# EasyEda_Gateway.net
KiCad netlist of a schematic drawn in EasyEDA Pro
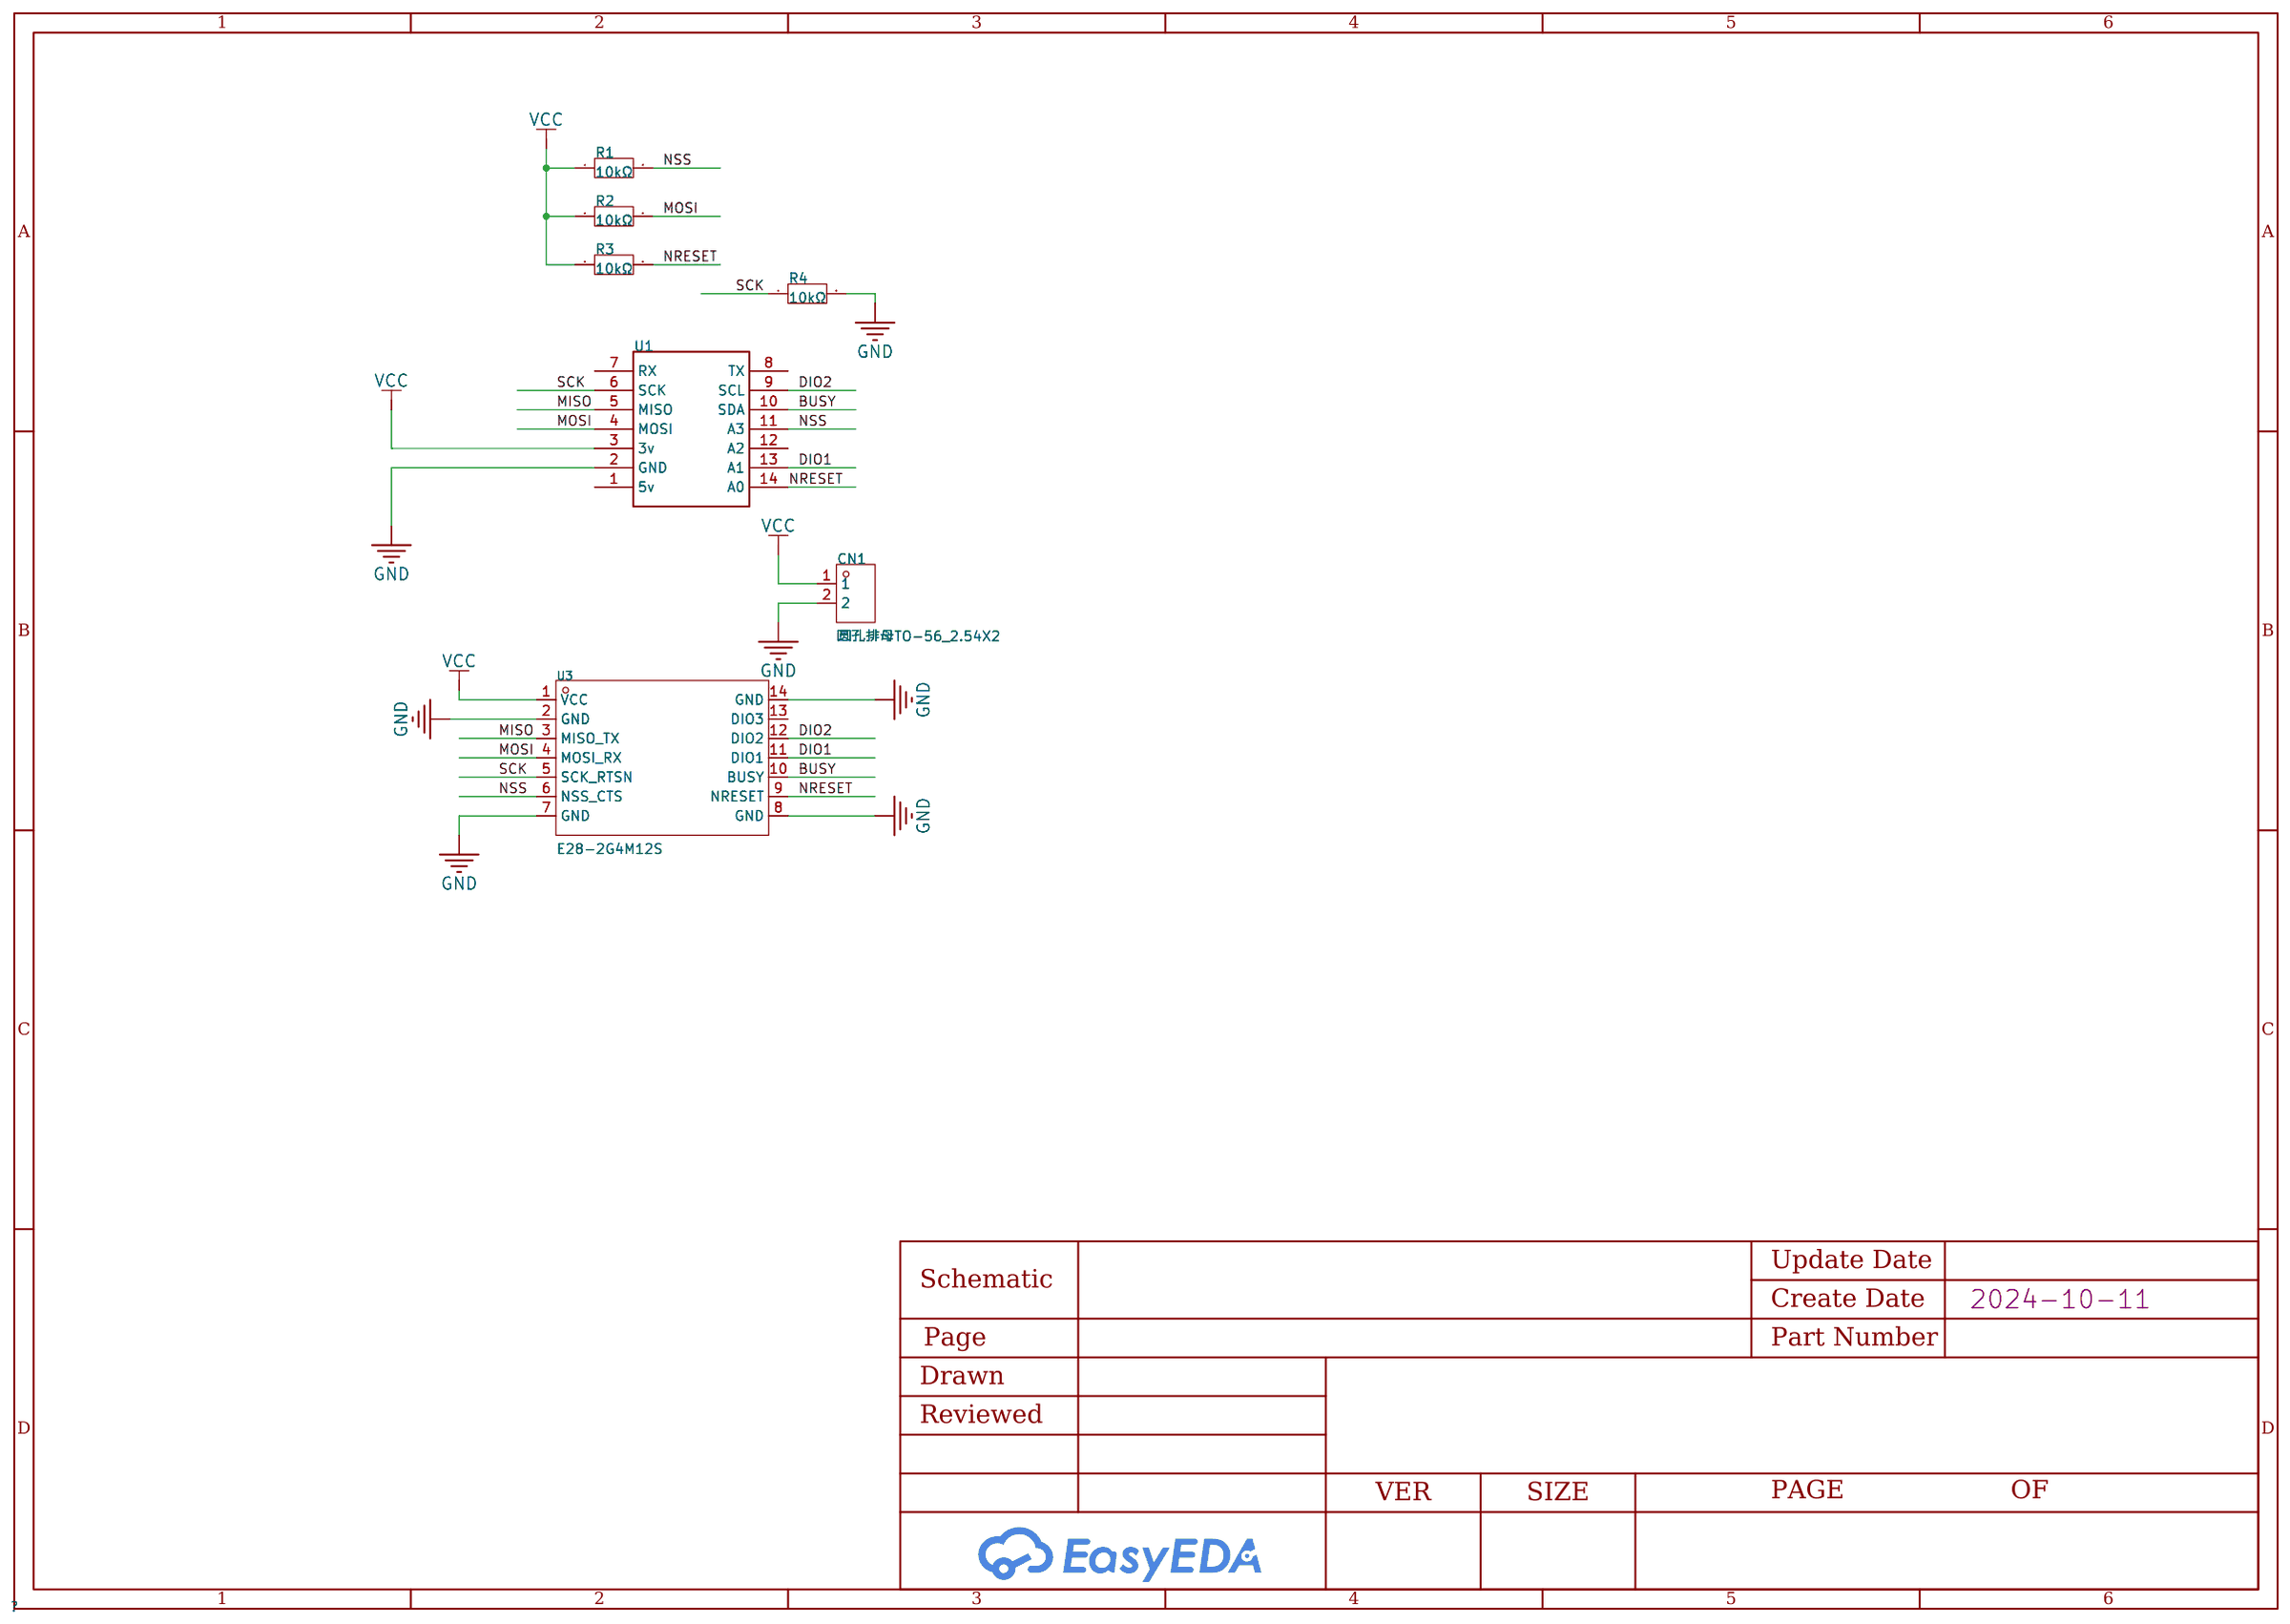
[diagram p0: schematic sheet]

(export (version "E")
  (design (tool "Eeschema 10.0.6"))
  (components
    (comp (ref "CN1")
      (value "圆孔排母TO-56_2.54X2")
      (footprint "easyedapro:CONN-TH_TO-56_2.54-2")
      (libsource (lib "easyedapro") (part "圆孔排母TO-56_2.54X2"))
    )
    (comp (ref "R1")
      (value "10kΩ")
      (footprint "easyedapro:R0603")
      (fields
        (field (name "Manufacturer Part") "RMCF0603FT1K00")
        (field (name "Manufacturer") "SEI(Stackpole Electronics Inc.)")
      )
      (libsource (lib "easyedapro") (part "RMCF0603FT1K00"))
    )
    (comp (ref "R2")
      (value "10kΩ")
      (footprint "easyedapro:R0603")
      (fields
        (field (name "Manufacturer Part") "RMCF0603FT1K00")
        (field (name "Manufacturer") "SEI(Stackpole Electronics Inc.)")
      )
      (libsource (lib "easyedapro") (part "RMCF0603FT1K00"))
    )
    (comp (ref "R3")
      (value "10kΩ")
      (footprint "easyedapro:R0603")
      (fields
        (field (name "Manufacturer Part") "RMCF0603FT1K00")
        (field (name "Manufacturer") "SEI(Stackpole Electronics Inc.)")
      )
      (libsource (lib "easyedapro") (part "RMCF0603FT1K00"))
    )
    (comp (ref "R4")
      (value "10kΩ")
      (footprint "easyedapro:R0603")
      (fields
        (field (name "Manufacturer Part") "RMCF0603FT1K00")
        (field (name "Manufacturer") "SEI(Stackpole Electronics Inc.)")
      )
      (libsource (lib "easyedapro") (part "RMCF0603FT1K00"))
    )
    (comp (ref "U1")
      (value "=ESP32-qtpy")
      (footprint "easyedapro:esp32-s2_qtpy")
      (libsource (lib "easyedapro") (part "esp32-s2_qtpy"))
    )
    (comp (ref "U3")
      (value "E28-2G4M12S")
      (footprint "easyedapro:WIRELM-SMD_E28-2G4M12S")
      (fields (field (name "Manufacturer") "EBYTE(亿佰特)"))
      (libsource (lib "easyedapro") (part "E28-2G4M12S"))
    )
  )
  (nets
    (net (code "1") (name "/BUSY") (class "Default")
      (node (ref "U1") (pin "10") (pinfunction "SDA_10") (pintype "input"))
      (node (ref "U3") (pin "10") (pinfunction "BUSY_10") (pintype "input"))
    )
    (net (code "2") (name "/DIO1") (class "Default")
      (node (ref "U1") (pin "13") (pinfunction "A1_13") (pintype "input"))
      (node (ref "U3") (pin "11") (pinfunction "DIO1_11") (pintype "input"))
    )
    (net (code "3") (name "/DIO2") (class "Default")
      (node (ref "U1") (pin "9") (pinfunction "SCL_9") (pintype "input"))
      (node (ref "U3") (pin "12") (pinfunction "DIO2_12") (pintype "input"))
    )
    (net (code "4") (name "/MISO") (class "Default")
      (node (ref "U1") (pin "5") (pinfunction "MISO_5") (pintype "input"))
      (node (ref "U3") (pin "3") (pinfunction "MISO_TX_3") (pintype "input"))
    )
    (net (code "5") (name "/MOSI") (class "Default")
      (node (ref "R2") (pin "2") (pinfunction "2_2") (pintype "input"))
      (node (ref "U1") (pin "4") (pinfunction "MOSI_4") (pintype "input"))
      (node (ref "U3") (pin "4") (pinfunction "MOSI_RX_4") (pintype "input"))
    )
    (net (code "6") (name "/NRESET") (class "Default")
      (node (ref "R3") (pin "2") (pinfunction "2_2") (pintype "input"))
      (node (ref "U1") (pin "14") (pinfunction "A0_14") (pintype "input"))
      (node (ref "U3") (pin "9") (pinfunction "NRESET_9") (pintype "input"))
    )
    (net (code "7") (name "/NSS") (class "Default")
      (node (ref "R1") (pin "2") (pinfunction "2_2") (pintype "input"))
      (node (ref "U1") (pin "11") (pinfunction "A3_11") (pintype "input"))
      (node (ref "U3") (pin "6") (pinfunction "NSS_CTS_6") (pintype "input"))
    )
    (net (code "8") (name "/SCK") (class "Default")
      (node (ref "R4") (pin "1") (pinfunction "1_1") (pintype "input"))
      (node (ref "U1") (pin "6") (pinfunction "SCK_6") (pintype "input"))
      (node (ref "U3") (pin "5") (pinfunction "SCK_RTSN_5") (pintype "input"))
    )
    (net (code "9") (name "GND") (class "Default")
      (node (ref "CN1") (pin "2") (pinfunction "2_2") (pintype "unspecified"))
      (node (ref "R4") (pin "2") (pinfunction "2_2") (pintype "input"))
      (node (ref "U1") (pin "2") (pinfunction "GND_2") (pintype "input"))
      (node (ref "U3") (pin "14") (pinfunction "GND_14") (pintype "input"))
      (node (ref "U3") (pin "2") (pinfunction "GND_2") (pintype "input"))
      (node (ref "U3") (pin "7") (pinfunction "GND_7") (pintype "input"))
      (node (ref "U3") (pin "8") (pinfunction "GND_8") (pintype "input"))
    )
    (net (code "10") (name "VCC") (class "Default")
      (node (ref "CN1") (pin "1") (pinfunction "1_1") (pintype "unspecified"))
      (node (ref "R1") (pin "1") (pinfunction "1_1") (pintype "input"))
      (node (ref "R2") (pin "1") (pinfunction "1_1") (pintype "input"))
      (node (ref "R3") (pin "1") (pinfunction "1_1") (pintype "input"))
      (node (ref "U1") (pin "3") (pinfunction "3v_3") (pintype "input"))
      (node (ref "U3") (pin "1") (pinfunction "VCC_1") (pintype "input"))
    )
    (net (code "11") (name "unconnected-(U1-5v-Pad1)") (class "Default")
      (node (ref "U1") (pin "1") (pinfunction "5v_1") (pintype "input"))
    )
    (net (code "12") (name "unconnected-(U1-A2-Pad12)") (class "Default")
      (node (ref "U1") (pin "12") (pinfunction "A2_12") (pintype "input"))
    )
    (net (code "13") (name "unconnected-(U1-RX-Pad7)") (class "Default")
      (node (ref "U1") (pin "7") (pinfunction "RX_7") (pintype "input"))
    )
    (net (code "14") (name "unconnected-(U1-TX-Pad8)") (class "Default")
      (node (ref "U1") (pin "8") (pinfunction "TX_8") (pintype "input"))
    )
    (net (code "15") (name "unconnected-(U3-DIO3-Pad13)") (class "Default")
      (node (ref "U3") (pin "13") (pinfunction "DIO3_13") (pintype "input"))
    )
  )
)
